# SmartCar_ESP_V4.net
KiCad netlist of a schematic drawn in EAGLE
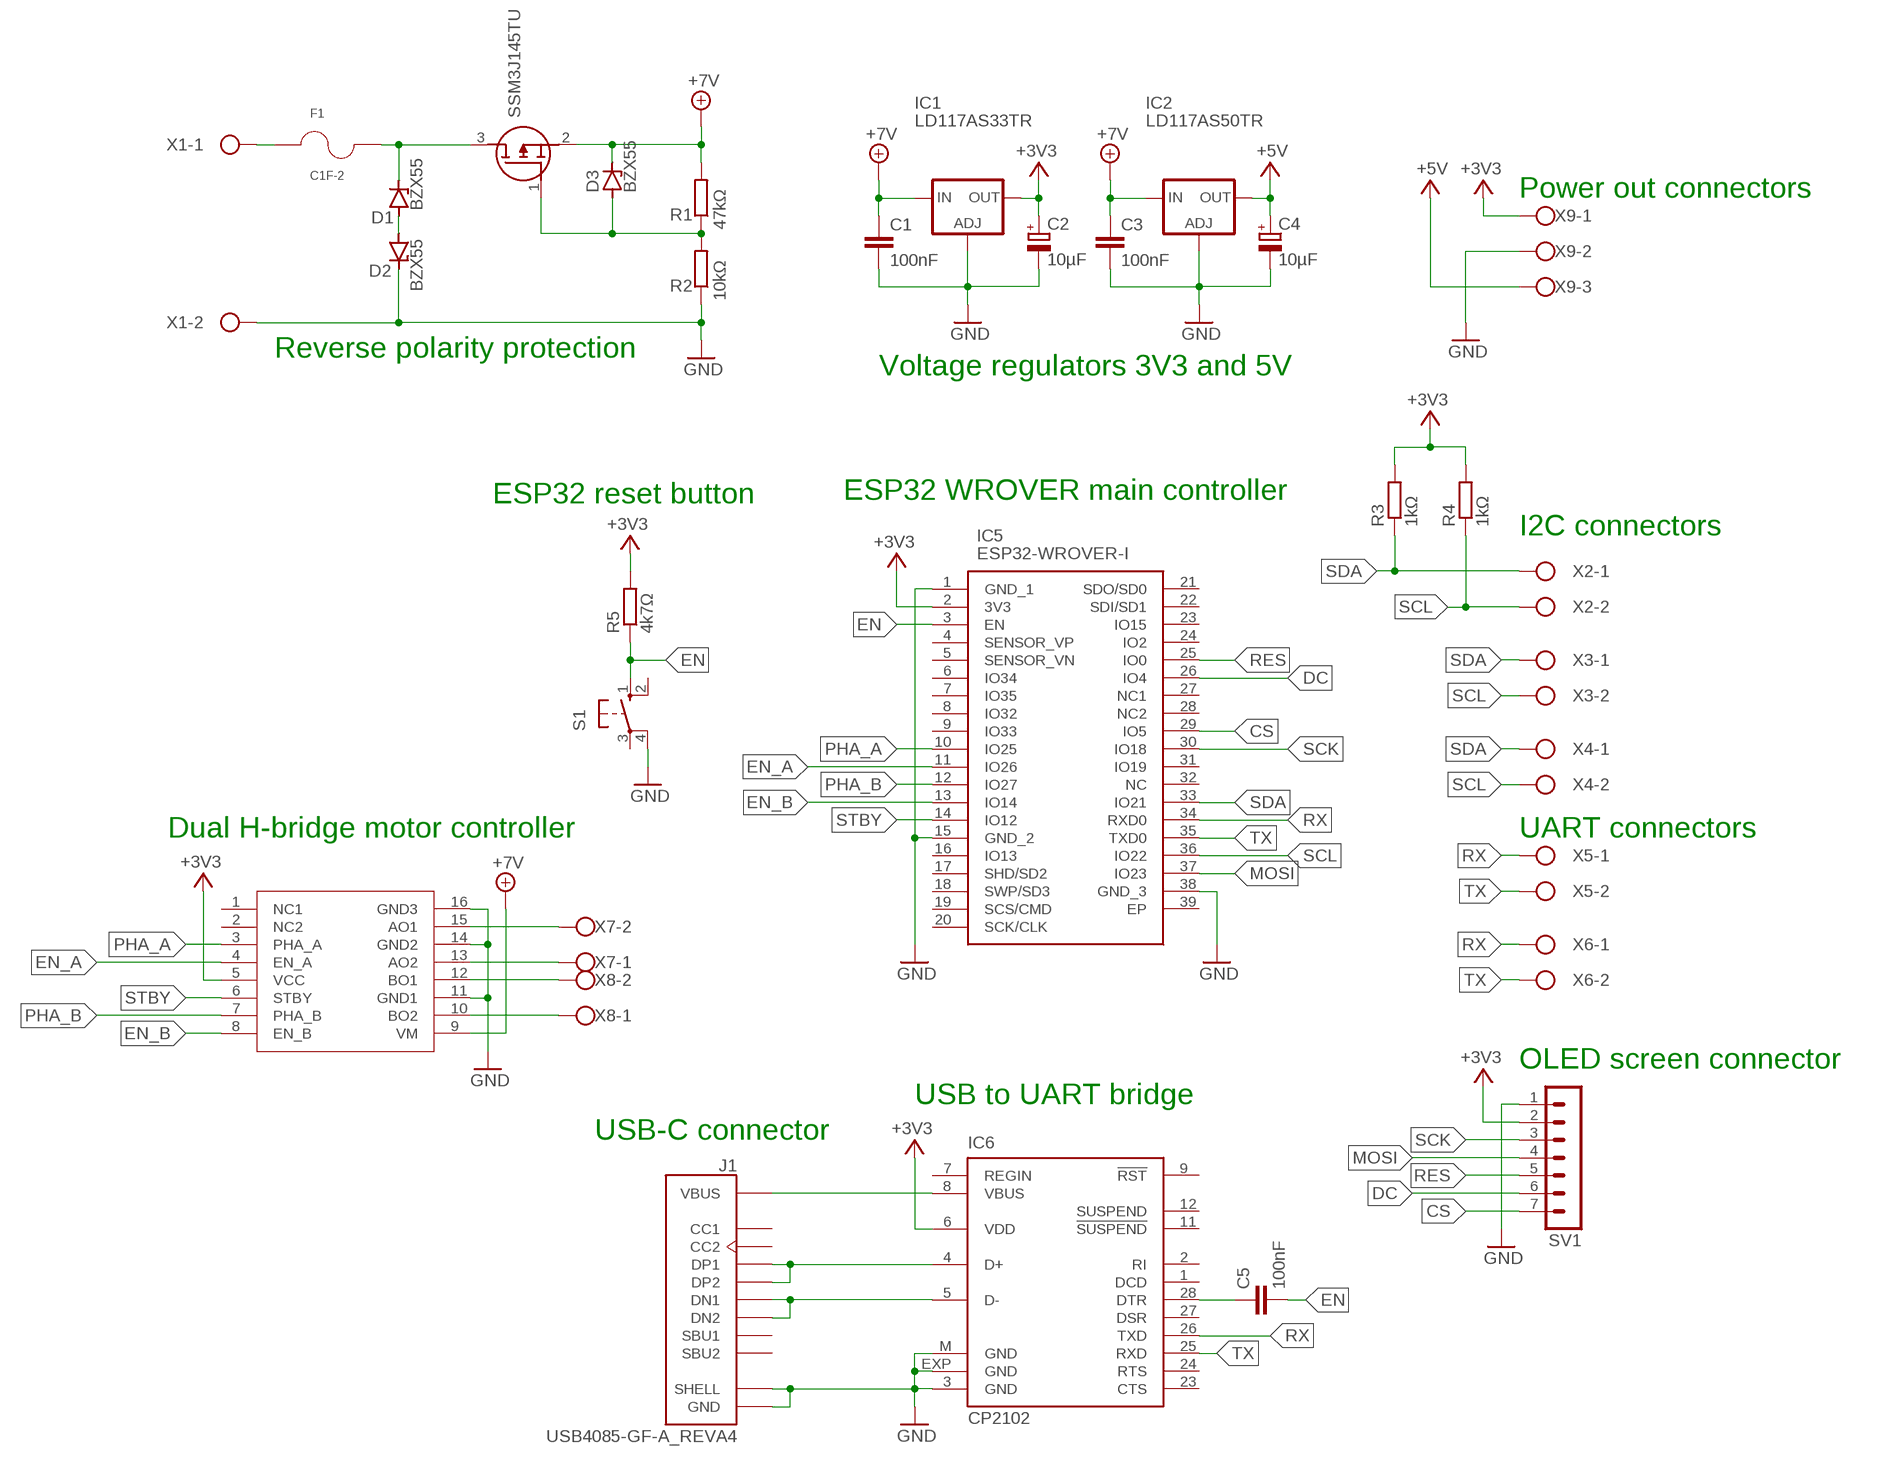
[diagram p0: schematic, sheet 1]

(export (version "E")
  (design (tool "Eeschema 10.0.6"))
  (components
    (comp (ref "C1")
      (value "100nF")
      (footprint "eagle-import:C0805")
      (libsource (lib "eagle-import") (part "C-EUC0805"))
    )
    (comp (ref "C2")
      (value "10µF")
      (footprint "eagle-import:E2,5-6E")
      (libsource (lib "eagle-import") (part "CPOL-EUE2,5-6E"))
    )
    (comp (ref "C3")
      (value "100nF")
      (footprint "eagle-import:C0805")
      (libsource (lib "eagle-import") (part "C-EUC0805"))
    )
    (comp (ref "C4")
      (value "10µF")
      (footprint "eagle-import:E2,5-6E")
      (libsource (lib "eagle-import") (part "CPOL-EUE2,5-6E"))
    )
    (comp (ref "C5")
      (value "100nF")
      (footprint "eagle-import:C0805")
      (libsource (lib "eagle-import") (part "C-EUC0805"))
    )
    (comp (ref "D1")
      (value "BZX55")
      (footprint "eagle-import:DO35Z10")
      (libsource (lib "eagle-import") (part "BZX55"))
    )
    (comp (ref "D2")
      (value "BZX55")
      (footprint "eagle-import:DO35Z10")
      (libsource (lib "eagle-import") (part "BZX55"))
    )
    (comp (ref "D3")
      (value "BZX55")
      (footprint "eagle-import:DO35Z10")
      (libsource (lib "eagle-import") (part "BZX55"))
    )
    (comp (ref "F1")
      (value "C1F-2")
      (footprint "eagle-import:FUSC3215X83N")
      (fields (field (name "MANUFACTURER") "Bel Fuse Inc."))
      (libsource (lib "eagle-import") (part "C1F-2"))
    )
    (comp (ref "IC1")
      (value "LD117AS33TR")
      (footprint "eagle-import:SOT223")
      (libsource (lib "eagle-import") (part "LD117A?S33TR"))
    )
    (comp (ref "IC2")
      (value "LD117AS50TR")
      (footprint "eagle-import:SOT223")
      (libsource (lib "eagle-import") (part "LD117A?S50TR"))
    )
    (comp (ref "IC5")
      (value "ESP32-WROVER-I")
      (footprint "eagle-import:ESP32WROVERI")
      (fields (field (name "MOUSER_PART_NUMBER") "356-ESP32-WROVER-I"))
      (libsource (lib "eagle-import") (part "ESP32-WROVER-I"))
    )
    (comp (ref "IC6")
      (value "CP2102")
      (footprint "eagle-import:MLP28")
      (fields (field (name "MF") "FARNELL") (field (name "MPN") "CP2102-GM"))
      (libsource (lib "eagle-import") (part "CP2102"))
    )
    (comp (ref "J1")
      (value "USB4085-GF-A_REVA4")
      (footprint "eagle-import:GCT_USB4085-GF-A_REVA4")
      (fields (field (name "MF") "Global Connector Technology") (field (name "MP") "USB4085-GF-A"))
      (libsource (lib "eagle-import") (part "USB4085-GF-A_REVA4"))
    )
    (comp (ref "R1")
      (value "47kΩ")
      (footprint "eagle-import:R0805")
      (libsource (lib "eagle-import") (part "R-EU_R0805"))
    )
    (comp (ref "R2")
      (value "10kΩ")
      (footprint "eagle-import:R0805")
      (libsource (lib "eagle-import") (part "R-EU_R0805"))
    )
    (comp (ref "R3")
      (value "1kΩ")
      (footprint "eagle-import:R0805")
      (libsource (lib "eagle-import") (part "R-EU_R0805"))
    )
    (comp (ref "R4")
      (value "1kΩ")
      (footprint "eagle-import:R0805")
      (libsource (lib "eagle-import") (part "R-EU_R0805"))
    )
    (comp (ref "R5")
      (value "4k7Ω")
      (footprint "eagle-import:R0805")
      (libsource (lib "eagle-import") (part "R-EU_R0805"))
    )
    (comp (ref "S1")
      (value "0")
      (footprint "eagle-import:B3F-10XX")
      (fields (field (name "MPN") "B3F-1000"))
      (libsource (lib "eagle-import") (part "10-XX"))
    )
    (comp (ref "SV1")
      (value "0")
      (footprint "eagle-import:MA07-1")
      (libsource (lib "eagle-import") (part "MA07-1"))
    )
    (comp (ref "U$1")
      (value "TC78H621FNG")
      (footprint "eagle-import:SOP65P640X110-16N")
      (libsource (lib "eagle-import") (part "TC78H621FNG"))
    )
    (comp (ref "U$2")
      (value "SSM3J145TU")
      (footprint "eagle-import:SOTFL65P210X75-3N")
      (libsource (lib "eagle-import") (part "SSM3J145TU"))
    )
    (comp (ref "X1")
      (value "0")
      (footprint "eagle-import:W237-102")
      (fields (field (name "MPN") "237-102"))
      (libsource (lib "eagle-import") (part "W237-102"))
    )
    (comp (ref "X2")
      (value "0")
      (footprint "eagle-import:W237-102")
      (fields (field (name "MPN") "237-102"))
      (libsource (lib "eagle-import") (part "W237-102"))
    )
    (comp (ref "X3")
      (value "0")
      (footprint "eagle-import:W237-102")
      (fields (field (name "MPN") "237-102"))
      (libsource (lib "eagle-import") (part "W237-102"))
    )
    (comp (ref "X4")
      (value "0")
      (footprint "eagle-import:W237-102")
      (fields (field (name "MPN") "237-102"))
      (libsource (lib "eagle-import") (part "W237-102"))
    )
    (comp (ref "X5")
      (value "0")
      (footprint "eagle-import:W237-102")
      (fields (field (name "MPN") "237-102"))
      (libsource (lib "eagle-import") (part "W237-102"))
    )
    (comp (ref "X6")
      (value "0")
      (footprint "eagle-import:W237-102")
      (fields (field (name "MPN") "237-102"))
      (libsource (lib "eagle-import") (part "W237-102"))
    )
    (comp (ref "X7")
      (value "0")
      (footprint "eagle-import:W237-102")
      (fields (field (name "MPN") "237-102"))
      (libsource (lib "eagle-import") (part "W237-102"))
    )
    (comp (ref "X8")
      (value "0")
      (footprint "eagle-import:W237-102")
      (fields (field (name "MPN") "237-102"))
      (libsource (lib "eagle-import") (part "W237-102"))
    )
    (comp (ref "X9")
      (value "0")
      (footprint "eagle-import:W237-103")
      (fields (field (name "MPN") "237-103"))
      (libsource (lib "eagle-import") (part "W237-103"))
    )
  )
  (nets
    (net (code "1") (name "+3V3") (class "Default")
      (node (ref "C2") (pin "+") (pinfunction "+_+") (pintype "passive"))
      (node (ref "IC1") (pin "4") (pinfunction "OUT_4") (pintype "passive"))
      (node (ref "IC5") (pin "2") (pinfunction "3V3_2") (pintype "bidirectional"))
      (node (ref "IC6") (pin "6") (pinfunction "VDD_6") (pintype "power_in"))
      (node (ref "R3") (pin "2") (pinfunction "2_2") (pintype "passive"))
      (node (ref "R4") (pin "2") (pinfunction "2_2") (pintype "passive"))
      (node (ref "R5") (pin "2") (pinfunction "2_2") (pintype "passive"))
      (node (ref "SV1") (pin "2") (pinfunction "2_2") (pintype "passive"))
      (node (ref "U$1") (pin "5") (pinfunction "VCC_5") (pintype "bidirectional"))
      (node (ref "X9") (pin "1") (pinfunction "KL_1") (pintype "passive"))
    )
    (net (code "2") (name "+5V") (class "Default")
      (node (ref "C4") (pin "+") (pinfunction "+_+") (pintype "passive"))
      (node (ref "IC2") (pin "4") (pinfunction "OUT_4") (pintype "passive"))
      (node (ref "X9") (pin "3") (pinfunction "KL_3") (pintype "passive"))
    )
    (net (code "3") (name "+7V") (class "Default")
      (node (ref "C1") (pin "1") (pinfunction "1_1") (pintype "passive"))
      (node (ref "C3") (pin "1") (pinfunction "1_1") (pintype "passive"))
      (node (ref "D3") (pin "C") (pinfunction "C_C") (pintype "passive"))
      (node (ref "IC1") (pin "3") (pinfunction "IN_3") (pintype "input"))
      (node (ref "IC2") (pin "3") (pinfunction "IN_3") (pintype "input"))
      (node (ref "R1") (pin "2") (pinfunction "2_2") (pintype "passive"))
      (node (ref "U$1") (pin "9") (pinfunction "VM_9") (pintype "bidirectional"))
      (node (ref "U$2") (pin "2") (pinfunction "S_2") (pintype "bidirectional"))
    )
    (net (code "4") (name "CS") (class "Default")
      (node (ref "IC5") (pin "29") (pinfunction "IO5_29") (pintype "bidirectional"))
      (node (ref "SV1") (pin "7") (pinfunction "7_7") (pintype "passive"))
    )
    (net (code "5") (name "DC") (class "Default")
      (node (ref "IC5") (pin "26") (pinfunction "IO4_26") (pintype "bidirectional"))
      (node (ref "SV1") (pin "6") (pinfunction "6_6") (pintype "passive"))
    )
    (net (code "6") (name "EN") (class "Default")
      (node (ref "C5") (pin "2") (pinfunction "2_2") (pintype "passive"))
      (node (ref "IC5") (pin "3") (pinfunction "EN_3") (pintype "bidirectional"))
      (node (ref "R5") (pin "1") (pinfunction "1_1") (pintype "passive"))
      (node (ref "S1") (pin "1") (pinfunction "S_1") (pintype "passive"))
    )
    (net (code "7") (name "EN_A") (class "Default")
      (node (ref "IC5") (pin "11") (pinfunction "IO26_11") (pintype "bidirectional"))
      (node (ref "U$1") (pin "4") (pinfunction "EN_A_4") (pintype "bidirectional"))
    )
    (net (code "8") (name "EN_B") (class "Default")
      (node (ref "IC5") (pin "13") (pinfunction "IO14_13") (pintype "bidirectional"))
      (node (ref "U$1") (pin "8") (pinfunction "EN_B_8") (pintype "bidirectional"))
    )
    (net (code "9") (name "GND") (class "Default")
      (node (ref "C1") (pin "2") (pinfunction "2_2") (pintype "passive"))
      (node (ref "C2") (pin "-") (pinfunction "-_-") (pintype "passive"))
      (node (ref "C3") (pin "2") (pinfunction "2_2") (pintype "passive"))
      (node (ref "C4") (pin "-") (pinfunction "-_-") (pintype "passive"))
      (node (ref "D2") (pin "C") (pinfunction "C_C") (pintype "passive"))
      (node (ref "IC1") (pin "1") (pinfunction "ADJ_1") (pintype "input"))
      (node (ref "IC2") (pin "1") (pinfunction "ADJ_1") (pintype "input"))
      (node (ref "IC5") (pin "1") (pinfunction "GND_1_1") (pintype "bidirectional"))
      (node (ref "IC5") (pin "15") (pinfunction "GND_2_15") (pintype "bidirectional"))
      (node (ref "IC5") (pin "38") (pinfunction "GND_3_38") (pintype "bidirectional"))
      (node (ref "IC6") (pin "3") (pinfunction "GND_3") (pintype "power_in"))
      (node (ref "IC6") (pin "EXP") (pinfunction "GND_EXP") (pintype "power_in"))
      (node (ref "IC6") (pin "M") (pinfunction "GND_M") (pintype "power_in"))
      (node (ref "J1") (pin "A1") (pinfunction "GND_A1") (pintype "passive"))
      (node (ref "J1") (pin "A12") (pinfunction "GND_A12") (pintype "passive"))
      (node (ref "J1") (pin "B1") (pinfunction "GND_B1") (pintype "passive"))
      (node (ref "J1") (pin "B12") (pinfunction "GND_B12") (pintype "passive"))
      (node (ref "J1") (pin "P1") (pinfunction "SHELL_P1") (pintype "passive"))
      (node (ref "J1") (pin "P2") (pinfunction "SHELL_P2") (pintype "passive"))
      (node (ref "J1") (pin "P3") (pinfunction "SHELL_P3") (pintype "passive"))
      (node (ref "J1") (pin "P4") (pinfunction "SHELL_P4") (pintype "passive"))
      (node (ref "R2") (pin "1") (pinfunction "1_1") (pintype "passive"))
      (node (ref "S1") (pin "4") (pinfunction "P1_4") (pintype "passive"))
      (node (ref "SV1") (pin "1") (pinfunction "1_1") (pintype "passive"))
      (node (ref "U$1") (pin "11") (pinfunction "GND1_11") (pintype "bidirectional"))
      (node (ref "U$1") (pin "14") (pinfunction "GND2_14") (pintype "bidirectional"))
      (node (ref "U$1") (pin "16") (pinfunction "GND3_16") (pintype "bidirectional"))
      (node (ref "X1") (pin "2") (pinfunction "KL_2") (pintype "passive"))
      (node (ref "X9") (pin "2") (pinfunction "KL_2") (pintype "passive"))
    )
    (net (code "10") (name "MOSI") (class "Default")
      (node (ref "IC5") (pin "37") (pinfunction "IO23_37") (pintype "bidirectional"))
      (node (ref "SV1") (pin "4") (pinfunction "4_4") (pintype "passive"))
    )
    (net (code "11") (name "Net-(D1-PadA)") (class "Default")
      (node (ref "D1") (pin "A") (pinfunction "A_A") (pintype "passive"))
      (node (ref "D2") (pin "A") (pinfunction "A_A") (pintype "passive"))
    )
    (net (code "12") (name "Net-(IC6-D+)") (class "Default")
      (node (ref "IC6") (pin "4") (pinfunction "D+_4") (pintype "bidirectional"))
      (node (ref "J1") (pin "A6") (pinfunction "DP1_A6") (pintype "bidirectional"))
      (node (ref "J1") (pin "B6") (pinfunction "DP2_B6") (pintype "bidirectional"))
    )
    (net (code "13") (name "Net-(IC6-D-)") (class "Default")
      (node (ref "IC6") (pin "5") (pinfunction "D-_5") (pintype "bidirectional"))
      (node (ref "J1") (pin "A7") (pinfunction "DN1_A7") (pintype "bidirectional"))
      (node (ref "J1") (pin "B7") (pinfunction "DN2_B7") (pintype "bidirectional"))
    )
    (net (code "14") (name "Net-(IC6-DTR)") (class "Default")
      (node (ref "C5") (pin "1") (pinfunction "1_1") (pintype "passive"))
      (node (ref "IC6") (pin "28") (pinfunction "DTR_28") (pintype "output"))
    )
    (net (code "15") (name "Net-(IC6-VBUS)") (class "Default")
      (node (ref "IC6") (pin "8") (pinfunction "VBUS_8") (pintype "input"))
      (node (ref "J1") (pin "A4") (pinfunction "VBUS_A4") (pintype "power_in"))
      (node (ref "J1") (pin "A9") (pinfunction "VBUS_A9") (pintype "power_in"))
      (node (ref "J1") (pin "B4") (pinfunction "VBUS_B4") (pintype "power_in"))
      (node (ref "J1") (pin "B9") (pinfunction "VBUS_B9") (pintype "power_in"))
    )
    (net (code "16") (name "Net-(U$1-AO1)") (class "Default")
      (node (ref "U$1") (pin "15") (pinfunction "AO1_15") (pintype "bidirectional"))
      (node (ref "X7") (pin "2") (pinfunction "KL_2") (pintype "passive"))
    )
    (net (code "17") (name "Net-(U$1-AO2)") (class "Default")
      (node (ref "U$1") (pin "13") (pinfunction "AO2_13") (pintype "bidirectional"))
      (node (ref "X7") (pin "1") (pinfunction "KL_1") (pintype "passive"))
    )
    (net (code "18") (name "Net-(U$1-BO1)") (class "Default")
      (node (ref "U$1") (pin "12") (pinfunction "BO1_12") (pintype "bidirectional"))
      (node (ref "X8") (pin "2") (pinfunction "KL_2") (pintype "passive"))
    )
    (net (code "19") (name "Net-(U$1-BO2)") (class "Default")
      (node (ref "U$1") (pin "10") (pinfunction "BO2_10") (pintype "bidirectional"))
      (node (ref "X8") (pin "1") (pinfunction "KL_1") (pintype "passive"))
    )
    (net (code "20") (name "Net-(U$2-D)") (class "Default")
      (node (ref "D1") (pin "C") (pinfunction "C_C") (pintype "passive"))
      (node (ref "F1") (pin "2") (pinfunction "2_2") (pintype "passive"))
      (node (ref "U$2") (pin "3") (pinfunction "D_3") (pintype "bidirectional"))
    )
    (net (code "21") (name "Net-(U$2-G)") (class "Default")
      (node (ref "D3") (pin "A") (pinfunction "A_A") (pintype "passive"))
      (node (ref "R1") (pin "1") (pinfunction "1_1") (pintype "passive"))
      (node (ref "R2") (pin "2") (pinfunction "2_2") (pintype "passive"))
      (node (ref "U$2") (pin "1") (pinfunction "G_1") (pintype "bidirectional"))
    )
    (net (code "22") (name "Net-(X1A-KL)") (class "Default")
      (node (ref "F1") (pin "1") (pinfunction "1_1") (pintype "passive"))
      (node (ref "X1") (pin "1") (pinfunction "KL_1") (pintype "passive"))
    )
    (net (code "23") (name "PHA_A") (class "Default")
      (node (ref "IC5") (pin "10") (pinfunction "IO25_10") (pintype "bidirectional"))
      (node (ref "U$1") (pin "3") (pinfunction "PHA_A_3") (pintype "bidirectional"))
    )
    (net (code "24") (name "PHA_B") (class "Default")
      (node (ref "IC5") (pin "12") (pinfunction "IO27_12") (pintype "bidirectional"))
      (node (ref "U$1") (pin "7") (pinfunction "PHA_B_7") (pintype "bidirectional"))
    )
    (net (code "25") (name "RES") (class "Default")
      (node (ref "IC5") (pin "25") (pinfunction "IO0_25") (pintype "bidirectional"))
      (node (ref "SV1") (pin "5") (pinfunction "5_5") (pintype "passive"))
    )
    (net (code "26") (name "RX") (class "Default")
      (node (ref "IC5") (pin "34") (pinfunction "RXD0_34") (pintype "bidirectional"))
      (node (ref "IC6") (pin "26") (pinfunction "TXD_26") (pintype "output"))
      (node (ref "X5") (pin "1") (pinfunction "KL_1") (pintype "passive"))
      (node (ref "X6") (pin "1") (pinfunction "KL_1") (pintype "passive"))
    )
    (net (code "27") (name "SCK") (class "Default")
      (node (ref "IC5") (pin "30") (pinfunction "IO18_30") (pintype "bidirectional"))
      (node (ref "SV1") (pin "3") (pinfunction "3_3") (pintype "passive"))
    )
    (net (code "28") (name "SCL") (class "Default")
      (node (ref "IC5") (pin "36") (pinfunction "IO22_36") (pintype "bidirectional"))
      (node (ref "R4") (pin "1") (pinfunction "1_1") (pintype "passive"))
      (node (ref "X2") (pin "2") (pinfunction "KL_2") (pintype "passive"))
      (node (ref "X3") (pin "2") (pinfunction "KL_2") (pintype "passive"))
      (node (ref "X4") (pin "2") (pinfunction "KL_2") (pintype "passive"))
    )
    (net (code "29") (name "SDA") (class "Default")
      (node (ref "IC5") (pin "33") (pinfunction "IO21_33") (pintype "bidirectional"))
      (node (ref "R3") (pin "1") (pinfunction "1_1") (pintype "passive"))
      (node (ref "X2") (pin "1") (pinfunction "KL_1") (pintype "passive"))
      (node (ref "X3") (pin "1") (pinfunction "KL_1") (pintype "passive"))
      (node (ref "X4") (pin "1") (pinfunction "KL_1") (pintype "passive"))
    )
    (net (code "30") (name "STBY") (class "Default")
      (node (ref "IC5") (pin "14") (pinfunction "IO12_14") (pintype "bidirectional"))
      (node (ref "U$1") (pin "6") (pinfunction "STBY_6") (pintype "bidirectional"))
    )
    (net (code "31") (name "TX") (class "Default")
      (node (ref "IC5") (pin "35") (pinfunction "TXD0_35") (pintype "bidirectional"))
      (node (ref "IC6") (pin "25") (pinfunction "RXD_25") (pintype "input"))
      (node (ref "X5") (pin "2") (pinfunction "KL_2") (pintype "passive"))
      (node (ref "X6") (pin "2") (pinfunction "KL_2") (pintype "passive"))
    )
    (net (code "32") (name "unconnected-(IC5-EP-Pad39)") (class "Default")
      (node (ref "IC5") (pin "39") (pinfunction "EP_39") (pintype "bidirectional"))
    )
    (net (code "33") (name "unconnected-(IC5-IO2-Pad24)") (class "Default")
      (node (ref "IC5") (pin "24") (pinfunction "IO2_24") (pintype "bidirectional"))
    )
    (net (code "34") (name "unconnected-(IC5-IO13-Pad16)") (class "Default")
      (node (ref "IC5") (pin "16") (pinfunction "IO13_16") (pintype "bidirectional"))
    )
    (net (code "35") (name "unconnected-(IC5-IO15-Pad23)") (class "Default")
      (node (ref "IC5") (pin "23") (pinfunction "IO15_23") (pintype "bidirectional"))
    )
    (net (code "36") (name "unconnected-(IC5-IO19-Pad31)") (class "Default")
      (node (ref "IC5") (pin "31") (pinfunction "IO19_31") (pintype "bidirectional"))
    )
    (net (code "37") (name "unconnected-(IC5-IO32-Pad8)") (class "Default")
      (node (ref "IC5") (pin "8") (pinfunction "IO32_8") (pintype "bidirectional"))
    )
    (net (code "38") (name "unconnected-(IC5-IO33-Pad9)") (class "Default")
      (node (ref "IC5") (pin "9") (pinfunction "IO33_9") (pintype "bidirectional"))
    )
    (net (code "39") (name "unconnected-(IC5-IO34-Pad6)") (class "Default")
      (node (ref "IC5") (pin "6") (pinfunction "IO34_6") (pintype "bidirectional"))
    )
    (net (code "40") (name "unconnected-(IC5-IO35-Pad7)") (class "Default")
      (node (ref "IC5") (pin "7") (pinfunction "IO35_7") (pintype "bidirectional"))
    )
    (net (code "41") (name "unconnected-(IC5-NC-Pad32)") (class "Default")
      (node (ref "IC5") (pin "32") (pinfunction "NC_32") (pintype "no_connect"))
    )
    (net (code "42") (name "unconnected-(IC5-NC1-Pad27)") (class "Default")
      (node (ref "IC5") (pin "27") (pinfunction "NC1_27") (pintype "bidirectional"))
    )
    (net (code "43") (name "unconnected-(IC5-NC2-Pad28)") (class "Default")
      (node (ref "IC5") (pin "28") (pinfunction "NC2_28") (pintype "bidirectional"))
    )
    (net (code "44") (name "unconnected-(IC5-SCK{slash}CLK-Pad20)") (class "Default")
      (node (ref "IC5") (pin "20") (pinfunction "SCK/CLK_20") (pintype "bidirectional"))
    )
    (net (code "45") (name "unconnected-(IC5-SCS{slash}CMD-Pad19)") (class "Default")
      (node (ref "IC5") (pin "19") (pinfunction "SCS/CMD_19") (pintype "bidirectional"))
    )
    (net (code "46") (name "unconnected-(IC5-SDI{slash}SD1-Pad22)") (class "Default")
      (node (ref "IC5") (pin "22") (pinfunction "SDI/SD1_22") (pintype "bidirectional"))
    )
    (net (code "47") (name "unconnected-(IC5-SDO{slash}SD0-Pad21)") (class "Default")
      (node (ref "IC5") (pin "21") (pinfunction "SDO/SD0_21") (pintype "bidirectional"))
    )
    (net (code "48") (name "unconnected-(IC5-SENSOR_VN-Pad5)") (class "Default")
      (node (ref "IC5") (pin "5") (pinfunction "SENSOR_VN_5") (pintype "bidirectional"))
    )
    (net (code "49") (name "unconnected-(IC5-SENSOR_VP-Pad4)") (class "Default")
      (node (ref "IC5") (pin "4") (pinfunction "SENSOR_VP_4") (pintype "bidirectional"))
    )
    (net (code "50") (name "unconnected-(IC5-SHD{slash}SD2-Pad17)") (class "Default")
      (node (ref "IC5") (pin "17") (pinfunction "SHD/SD2_17") (pintype "bidirectional"))
    )
    (net (code "51") (name "unconnected-(IC5-SWP{slash}SD3-Pad18)") (class "Default")
      (node (ref "IC5") (pin "18") (pinfunction "SWP/SD3_18") (pintype "bidirectional"))
    )
    (net (code "52") (name "unconnected-(IC6-CTS-Pad23)") (class "Default")
      (node (ref "IC6") (pin "23") (pinfunction "CTS_23") (pintype "input"))
    )
    (net (code "53") (name "unconnected-(IC6-DCD-Pad1)") (class "Default")
      (node (ref "IC6") (pin "1") (pinfunction "DCD_1") (pintype "input"))
    )
    (net (code "54") (name "unconnected-(IC6-DSR-Pad27)") (class "Default")
      (node (ref "IC6") (pin "27") (pinfunction "DSR_27") (pintype "input"))
    )
    (net (code "55") (name "unconnected-(IC6-REGIN-Pad7)") (class "Default")
      (node (ref "IC6") (pin "7") (pinfunction "REGIN_7") (pintype "passive"))
    )
    (net (code "56") (name "unconnected-(IC6-RI-Pad2)") (class "Default")
      (node (ref "IC6") (pin "2") (pinfunction "RI_2") (pintype "input"))
    )
    (net (code "57") (name "unconnected-(IC6-RTS-Pad24)") (class "Default")
      (node (ref "IC6") (pin "24") (pinfunction "RTS_24") (pintype "output"))
    )
    (net (code "58") (name "unconnected-(IC6-SUSPEND-Pad12)") (class "Default")
      (node (ref "IC6") (pin "12") (pinfunction "SUSPEND_12") (pintype "output"))
    )
    (net (code "59") (name "unconnected-(IC6-~{RST}-Pad9)") (class "Default")
      (node (ref "IC6") (pin "9") (pinfunction "~{RST}_9") (pintype "bidirectional"))
    )
    (net (code "60") (name "unconnected-(IC6-~{SUSPEND}-Pad11)") (class "Default")
      (node (ref "IC6") (pin "11") (pinfunction "~{SUSPEND}_11") (pintype "output"))
    )
    (net (code "61") (name "unconnected-(J1-CC1-PadA5)") (class "Default")
      (node (ref "J1") (pin "A5") (pinfunction "CC1_A5") (pintype "bidirectional"))
    )
    (net (code "62") (name "unconnected-(J1-CC2-PadB5)") (class "Default")
      (node (ref "J1") (pin "B5") (pinfunction "CC2_B5") (pintype "bidirectional"))
    )
    (net (code "63") (name "unconnected-(J1-SBU1-PadA8)") (class "Default")
      (node (ref "J1") (pin "A8") (pinfunction "SBU1_A8") (pintype "bidirectional"))
    )
    (net (code "64") (name "unconnected-(J1-SBU2-PadB8)") (class "Default")
      (node (ref "J1") (pin "B8") (pinfunction "SBU2_B8") (pintype "bidirectional"))
    )
    (net (code "65") (name "unconnected-(S1-P-Pad3)") (class "Default")
      (node (ref "S1") (pin "3") (pinfunction "P_3") (pintype "passive"))
    )
    (net (code "66") (name "unconnected-(S1-S1-Pad2)") (class "Default")
      (node (ref "S1") (pin "2") (pinfunction "S1_2") (pintype "passive"))
    )
    (net (code "67") (name "unconnected-(U$1-NC1-Pad1)") (class "Default")
      (node (ref "U$1") (pin "1") (pinfunction "NC1_1") (pintype "bidirectional"))
    )
    (net (code "68") (name "unconnected-(U$1-NC2-Pad2)") (class "Default")
      (node (ref "U$1") (pin "2") (pinfunction "NC2_2") (pintype "bidirectional"))
    )
  )
)
